# 10-ESP32.net
KiCad netlist of a schematic drawn in Altium Designer
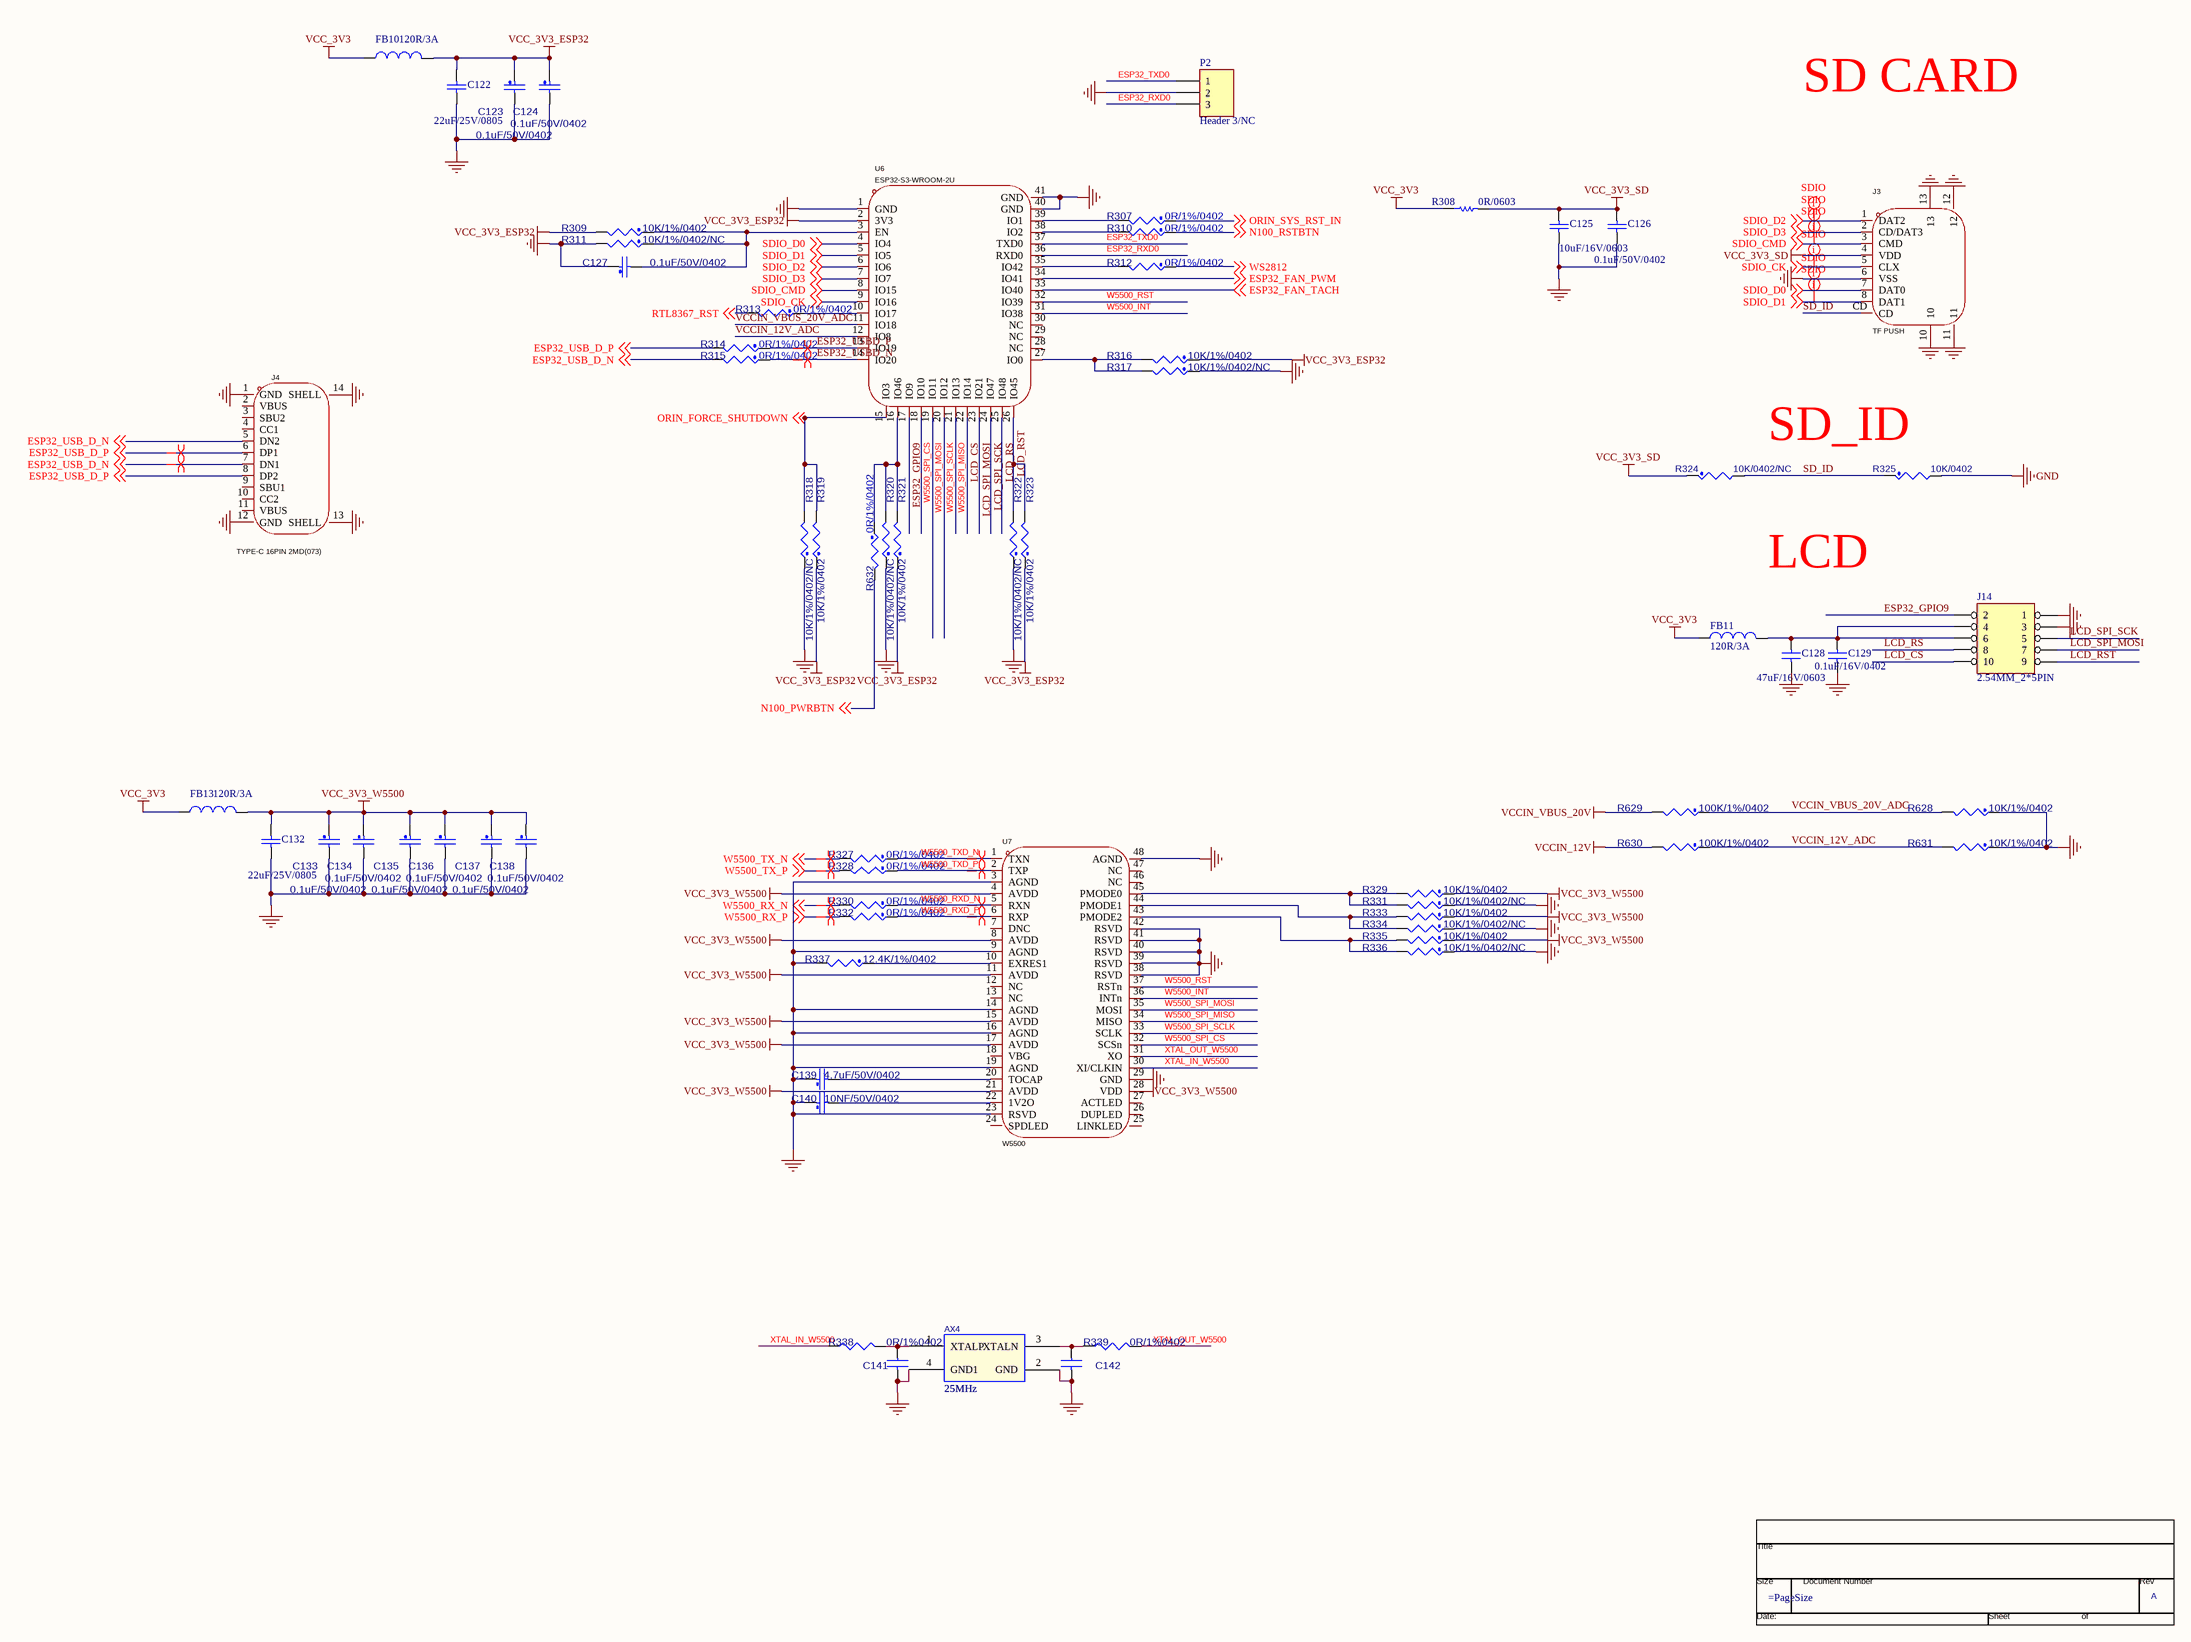
[diagram p0: 10-ESP32.SchDoc]

(export (version "E")
  (design (tool "Eeschema 10.0.6"))
  (components
    (comp (ref "AX4")
      (value "25MHz")
      (footprint "2016")
      (fields (field (name "ALTIUM_VALUE") "25MHz"))
      (libsource (lib "*") (part "XTAL_0"))
    )
    (comp (ref "C122")
      (value "22uF/25V/0805")
      (description "Capacitor")
      (fields (field (name "PUBLISHER") "Altium Limited"))
      (libsource (lib "LIBS") (part "CAP"))
    )
    (comp (ref "C123")
      (value "0.1uF/50V/0402")
      (footprint "C0402")
      (description "GCM155R71H104KE02/MURATA")
      (fields (field (name "TOLERANCE") "10%") (field (name "VOLTAGE") "16V"))
      (libsource (lib "*") (part "CAP_NP"))
    )
    (comp (ref "C124")
      (value "0.1uF/50V/0402")
      (footprint "C0402")
      (description "GCM155R71H104KE02/MURATA")
      (fields (field (name "TOLERANCE") "10%") (field (name "VOLTAGE") "16V"))
      (libsource (lib "*") (part "CAP_NP"))
    )
    (comp (ref "C125")
      (value "10uF/16V/0603")
      (description "Capacitor")
      (fields (field (name "Comment") "HGC0603R5106M160NTHJ") (field (name "PUBLISHER") "Altium Limited"))
      (libsource (lib "LIBS") (part "CAP"))
    )
    (comp (ref "C126")
      (value "0.1uF/50V/0402")
      (description "Capacitor")
      (fields (field (name "PUBLISHER") "Altium Limited"))
      (libsource (lib "LIBS") (part "CAP"))
    )
    (comp (ref "C127")
      (value "0.1uF/50V/0402")
      (footprint "C0402")
      (description "GCM155R71H104KE02/MURATA")
      (fields (field (name "TOLERANCE") "10%") (field (name "VOLTAGE") "16V"))
      (libsource (lib "*") (part "CAP_NP"))
    )
    (comp (ref "C128")
      (value "47uF/16V/0603")
      (description "Capacitor")
      (fields (field (name "PUBLISHER") "Altium Limited"))
      (libsource (lib "LIBS") (part "CAP"))
    )
    (comp (ref "C129")
      (value "0.1uF/16V/0402")
      (description "Capacitor")
      (fields (field (name "PUBLISHER") "Altium Limited"))
      (libsource (lib "LIBS") (part "CAP"))
    )
    (comp (ref "C132")
      (value "22uF/25V/0805")
      (description "Capacitor")
      (fields (field (name "PUBLISHER") "Altium Limited"))
      (libsource (lib "LIBS") (part "CAP"))
    )
    (comp (ref "C133")
      (value "0.1uF/50V/0402")
      (footprint "C0402")
      (description "GCM155R71H104KE02/MURATA")
      (fields (field (name "TOLERANCE") "10%") (field (name "VOLTAGE") "16V"))
      (libsource (lib "*") (part "CAP_NP"))
    )
    (comp (ref "C134")
      (value "0.1uF/50V/0402")
      (footprint "C0402")
      (description "GCM155R71H104KE02/MURATA")
      (fields (field (name "TOLERANCE") "10%") (field (name "VOLTAGE") "16V"))
      (libsource (lib "*") (part "CAP_NP"))
    )
    (comp (ref "C135")
      (value "0.1uF/50V/0402")
      (footprint "C0402")
      (description "GCM155R71H104KE02/MURATA")
      (fields (field (name "TOLERANCE") "10%") (field (name "VOLTAGE") "16V"))
      (libsource (lib "*") (part "CAP_NP"))
    )
    (comp (ref "C136")
      (value "0.1uF/50V/0402")
      (footprint "C0402")
      (description "GCM155R71H104KE02/MURATA")
      (fields (field (name "TOLERANCE") "10%") (field (name "VOLTAGE") "16V"))
      (libsource (lib "*") (part "CAP_NP"))
    )
    (comp (ref "C137")
      (value "0.1uF/50V/0402")
      (footprint "C0402")
      (description "GCM155R71H104KE02/MURATA")
      (fields (field (name "TOLERANCE") "10%") (field (name "VOLTAGE") "16V"))
      (libsource (lib "*") (part "CAP_NP"))
    )
    (comp (ref "C138")
      (value "0.1uF/50V/0402")
      (footprint "C0402")
      (description "GCM155R71H104KE02/MURATA")
      (fields (field (name "TOLERANCE") "10%") (field (name "VOLTAGE") "16V"))
      (libsource (lib "*") (part "CAP_NP"))
    )
    (comp (ref "C139")
      (value "4.7uF/50V/0402")
      (footprint "C0402")
      (description "GCM155R71H104KE02/MURATA")
      (fields (field (name "TOLERANCE") "10%") (field (name "VOLTAGE") "16V"))
      (libsource (lib "*") (part "CAP_NP"))
    )
    (comp (ref "C140")
      (value "10NF/50V/0402")
      (footprint "C0402")
      (description "GCM155R71H104KE02/MURATA")
      (fields (field (name "TOLERANCE") "10%") (field (name "VOLTAGE") "16V"))
      (libsource (lib "*") (part "CAP_NP"))
    )
    (comp (ref "C141") (value "CAP NP_Dup3") (footprint "C0402") (libsource (lib "*") (part "CAP NP_Dup3")))
    (comp (ref "C142") (value "CAP NP_Dup3") (footprint "C0402") (libsource (lib "*") (part "CAP NP_Dup3")))
    (comp (ref "FB10")
      (value "120R/3A")
      (footprint "L0603")
      (description "BLM18KG121TN1D")
      (fields (field (name "PUBLISHER") "Altium Limited"))
      (libsource (lib "") (part "Inductor_1"))
    )
    (comp (ref "FB11")
      (value "120R/3A")
      (footprint "L0603")
      (description "BLM18KG121TN1D")
      (fields (field (name "PUBLISHER") "Altium Limited"))
      (libsource (lib "LIBS") (part "Inductor"))
    )
    (comp (ref "FB13")
      (value "120R/3A")
      (footprint "L0603")
      (description "BLM18KG121TN1D")
      (fields (field (name "PUBLISHER") "Altium Limited"))
      (libsource (lib "") (part "Inductor_1"))
    )
    (comp (ref "J3")
      (value "TF PUSH")
      (footprint "TF-SMD_TF-PUSH")
      (fields (field (name "MANUFACTURER") "SHOU HAN(首韩)"))
      (libsource (lib "altium-import") (part "root_0_TF PUSH_"))
    )
    (comp (ref "J4")
      (value "TYPE-C 16PIN 2MD(073)")
      (footprint "USB-C-SMD_TYPE-C-6PIN-2MD-073")
      (fields (field (name "MANUFACTURER") "SHOU HAN(首韩)"))
      (libsource (lib "altium-import") (part "root_0_TYPE-C 16PIN 2MD(073)_"))
    )
    (comp (ref "J14")
      (value "2.54MM_2*5PIN")
      (footprint "IDC10")
      (libsource (lib "LIBS") (part "HEADER 5X2"))
    )
    (comp (ref "P2")
      (value "Header 3/NC")
      (footprint "HEADER3")
      (description "Header, 3-Pin")
      (fields (field (name "PUBLISHER") "Altium Limited"))
      (libsource (lib "LIBS") (part "Header 3"))
    )
    (comp (ref "R307")
      (value "0R/1%/0402")
      (footprint "R0402")
      (description "AC0402FR-070RL/YAGEO")
      (fields (field (name "TOLERANCE") "1%") (field (name "Comment") "RES_Dup2"))
      (libsource (lib "*") (part "RES_Dup2"))
    )
    (comp (ref "R308")
      (value "0R/0603")
      (footprint "R0603")
      (description "Semiconductor Resistor")
      (fields (field (name "PUBLISHER") "Altium Limited"))
      (libsource (lib "LIBS") (part "Res Semi"))
    )
    (comp (ref "R309")
      (value "10K/1%/0402")
      (footprint "R0402")
      (description "AC0402FR-0710KL/YAGEO")
      (fields (field (name "Comment") "RES_Dup2"))
      (libsource (lib "*") (part "RES_Dup2"))
    )
    (comp (ref "R310")
      (value "0R/1%/0402")
      (footprint "R0402")
      (description "AC0402FR-070RL/YAGEO")
      (fields (field (name "TOLERANCE") "1%") (field (name "Comment") "RES_Dup2"))
      (libsource (lib "*") (part "RES_Dup2"))
    )
    (comp (ref "R311")
      (value "10K/1%/0402/NC")
      (footprint "R0402")
      (description "AC0402FR-0710KL/YAGEO")
      (fields (field (name "Comment") "RES_Dup2"))
      (libsource (lib "*") (part "RES_Dup2"))
    )
    (comp (ref "R312")
      (value "0R/1%/0402")
      (footprint "R0402")
      (description "AC0402FR-070RL/YAGEO")
      (fields (field (name "TOLERANCE") "1%") (field (name "Comment") "RES_Dup2"))
      (libsource (lib "*") (part "RES_Dup2"))
    )
    (comp (ref "R313")
      (value "0R/1%/0402")
      (footprint "R0402")
      (description "AC0402FR-070RL/YAGEO")
      (fields (field (name "TOLERANCE") "1%") (field (name "Comment") "RES_Dup2"))
      (libsource (lib "*") (part "RES_Dup2"))
    )
    (comp (ref "R314")
      (value "0R/1%/0402")
      (footprint "R0402")
      (description "AC0402FR-070RL/YAGEO")
      (fields (field (name "TOLERANCE") "1%") (field (name "Comment") "RES_Dup2"))
      (libsource (lib "*") (part "RES_Dup2"))
    )
    (comp (ref "R315")
      (value "0R/1%/0402")
      (footprint "R0402")
      (description "AC0402FR-070RL/YAGEO")
      (fields (field (name "TOLERANCE") "1%") (field (name "Comment") "RES_Dup2"))
      (libsource (lib "*") (part "RES_Dup2"))
    )
    (comp (ref "R316")
      (value "10K/1%/0402")
      (footprint "R0402")
      (description "AC0402FR-0710KL/YAGEO")
      (fields (field (name "Comment") "RES_Dup2"))
      (libsource (lib "*") (part "RES_Dup2"))
    )
    (comp (ref "R317")
      (value "10K/1%/0402/NC")
      (footprint "R0402")
      (description "AC0402FR-0710KL/YAGEO")
      (fields (field (name "Comment") "RES_Dup2"))
      (libsource (lib "*") (part "RES_Dup2"))
    )
    (comp (ref "R318")
      (value "10K/1%/0402/NC")
      (footprint "R0402")
      (description "AC0402FR-0710KL/YAGEO")
      (fields (field (name "Comment") "RES_Dup2"))
      (libsource (lib "*") (part "RES_Dup2"))
    )
    (comp (ref "R319")
      (value "10K/1%/0402")
      (footprint "R0402")
      (description "AC0402FR-0710KL/YAGEO")
      (fields (field (name "Comment") "RES_Dup2"))
      (libsource (lib "*") (part "RES_Dup2"))
    )
    (comp (ref "R320")
      (value "10K/1%/0402/NC")
      (footprint "R0402")
      (description "AC0402FR-0710KL/YAGEO")
      (fields (field (name "Comment") "RES_Dup2"))
      (libsource (lib "*") (part "RES_Dup2"))
    )
    (comp (ref "R321")
      (value "10K/1%/0402")
      (footprint "R0402")
      (description "AC0402FR-0710KL/YAGEO")
      (fields (field (name "Comment") "RES_Dup2"))
      (libsource (lib "*") (part "RES_Dup2"))
    )
    (comp (ref "R322")
      (value "10K/1%/0402/NC")
      (footprint "R0402")
      (description "AC0402FR-0710KL/YAGEO")
      (fields (field (name "Comment") "RES_Dup2"))
      (libsource (lib "*") (part "RES_Dup2"))
    )
    (comp (ref "R323")
      (value "10K/1%/0402")
      (footprint "R0402")
      (description "AC0402FR-0710KL/YAGEO")
      (fields (field (name "Comment") "RES_Dup2"))
      (libsource (lib "*") (part "RES_Dup2"))
    )
    (comp (ref "R324")
      (value "10K/0402/NC")
      (footprint "R0402")
      (description "RES MF 1.0K 1/16W 5% 0402")
      (fields (field (name "TOLERANCE") "5%"))
      (libsource (lib "*") (part "RES_Dup1"))
    )
    (comp (ref "R325")
      (value "10K/0402")
      (footprint "R0402")
      (description "RES MF 1.0K 1/16W 5% 0402")
      (fields (field (name "TOLERANCE") "5%"))
      (libsource (lib "*") (part "RES_Dup1"))
    )
    (comp (ref "R327")
      (value "0R/1%/0402")
      (footprint "R0402")
      (description "AC0402FR-070RL/YAGEO")
      (fields (field (name "TOLERANCE") "1%") (field (name "Comment") "RES_Dup2"))
      (libsource (lib "*") (part "RES_Dup2"))
    )
    (comp (ref "R328")
      (value "0R/1%/0402")
      (footprint "R0402")
      (description "AC0402FR-070RL/YAGEO")
      (fields (field (name "TOLERANCE") "1%") (field (name "Comment") "RES_Dup2"))
      (libsource (lib "*") (part "RES_Dup2"))
    )
    (comp (ref "R329")
      (value "10K/1%/0402")
      (footprint "R0402")
      (description "AC0402FR-0710KL/YAGEO")
      (fields (field (name "Comment") "RES_Dup2"))
      (libsource (lib "*") (part "RES_Dup2"))
    )
    (comp (ref "R330")
      (value "0R/1%/0402")
      (footprint "R0402")
      (description "AC0402FR-070RL/YAGEO")
      (fields (field (name "TOLERANCE") "1%") (field (name "Comment") "RES_Dup2"))
      (libsource (lib "*") (part "RES_Dup2"))
    )
    (comp (ref "R331")
      (value "10K/1%/0402/NC")
      (footprint "R0402")
      (description "AC0402FR-0710KL/YAGEO")
      (fields (field (name "Comment") "RES_Dup2"))
      (libsource (lib "*") (part "RES_Dup2"))
    )
    (comp (ref "R332")
      (value "0R/1%/0402")
      (footprint "R0402")
      (description "AC0402FR-070RL/YAGEO")
      (fields (field (name "TOLERANCE") "1%") (field (name "Comment") "RES_Dup2"))
      (libsource (lib "*") (part "RES_Dup2"))
    )
    (comp (ref "R333")
      (value "10K/1%/0402")
      (footprint "R0402")
      (description "AC0402FR-0710KL/YAGEO")
      (fields (field (name "Comment") "RES_Dup2"))
      (libsource (lib "*") (part "RES_Dup2"))
    )
    (comp (ref "R334")
      (value "10K/1%/0402/NC")
      (footprint "R0402")
      (description "AC0402FR-0710KL/YAGEO")
      (fields (field (name "Comment") "RES_Dup2"))
      (libsource (lib "*") (part "RES_Dup2"))
    )
    (comp (ref "R335")
      (value "10K/1%/0402")
      (footprint "R0402")
      (description "AC0402FR-0710KL/YAGEO")
      (fields (field (name "Comment") "RES_Dup2"))
      (libsource (lib "*") (part "RES_Dup2"))
    )
    (comp (ref "R336")
      (value "10K/1%/0402/NC")
      (footprint "R0402")
      (description "AC0402FR-0710KL/YAGEO")
      (fields (field (name "Comment") "RES_Dup2"))
      (libsource (lib "*") (part "RES_Dup2"))
    )
    (comp (ref "R337")
      (value "12.4K/1%/0402")
      (footprint "R0402")
      (description "AC0402FR-0710KL/YAGEO")
      (fields (field (name "Comment") "RES_Dup2"))
      (libsource (lib "*") (part "RES_Dup2"))
    )
    (comp (ref "R338")
      (value "0R/1%0402")
      (footprint "R0402")
      (fields (field (name "Comment") "R_Dup3"))
      (libsource (lib "*") (part "R_Dup3"))
    )
    (comp (ref "R339")
      (value "0R/1%0402")
      (footprint "R0402")
      (fields (field (name "Comment") "R_Dup3"))
      (libsource (lib "*") (part "R_Dup3"))
    )
    (comp (ref "R628")
      (value "10K/1%/0402")
      (footprint "R0402")
      (description "AC0402FR-0710KL/YAGEO")
      (fields (field (name "Comment") "RES_Dup2"))
      (libsource (lib "*") (part "RES_Dup2"))
    )
    (comp (ref "R629")
      (value "100K/1%/0402")
      (footprint "R0402")
      (description "AC0402FR-0710KL/YAGEO")
      (fields (field (name "Comment") "RES_Dup2"))
      (libsource (lib "*") (part "RES_Dup2"))
    )
    (comp (ref "R630")
      (value "100K/1%/0402")
      (footprint "R0402")
      (description "AC0402FR-0710KL/YAGEO")
      (fields (field (name "Comment") "RES_Dup2"))
      (libsource (lib "*") (part "RES_Dup2"))
    )
    (comp (ref "R631")
      (value "10K/1%/0402")
      (footprint "R0402")
      (description "AC0402FR-0710KL/YAGEO")
      (fields (field (name "Comment") "RES_Dup2"))
      (libsource (lib "*") (part "RES_Dup2"))
    )
    (comp (ref "R632")
      (value "0R/1%/0402")
      (footprint "R0402")
      (description "AC0402FR-070RL/YAGEO")
      (fields (field (name "TOLERANCE") "1%") (field (name "Comment") "RES_Dup2"))
      (libsource (lib "*") (part "RES_Dup2"))
    )
    (comp (ref "U6")
      (value "ESP32-S3-WROOM-2U")
      (footprint "ESP32-S3-WROOM-2")
      (fields
        (field (name "MANUFACTURER") "ESPRESSIF(乐鑫)")
        (field (name "MANUFACTURER PART") "ESP32-S3-WROOM-2-N32R8V")
      )
      (libsource (lib "altium-import") (part "root_0_ESP32-S3-WROOM-2-N32R8V_"))
    )
    (comp (ref "U7")
      (value "W5500")
      (footprint "LQFP-48_L7.0-W7.0-P0.50-LS9.0-BL")
      (fields (field (name "MANUFACTURER") "WIZNET"))
      (libsource (lib "altium-import") (part "root_0_W5500_"))
    )
  )
  (nets
    (net (code "1") (name "/ESP32_GPIO9") (class "Default")
      (node (ref "J14") (pin "2") (pinfunction "2_2") (pintype "passive"))
      (node (ref "U6") (pin "17") (pinfunction "IO9_17") (pintype "passive"))
    )
    (net (code "2") (name "/ESP32_RXD0") (class "Default")
      (node (ref "P2") (pin "3") (pinfunction "3_3") (pintype "passive"))
      (node (ref "U6") (pin "36") (pinfunction "RXD0_36") (pintype "passive"))
    )
    (net (code "3") (name "/ESP32_TXD0") (class "Default")
      (node (ref "P2") (pin "1") (pinfunction "1_1") (pintype "passive"))
      (node (ref "U6") (pin "37") (pinfunction "TXD0_37") (pintype "passive"))
    )
    (net (code "4") (name "/ESP32_USBD_N") (class "Default")
      (node (ref "R315") (pin "1") (pinfunction "1_1") (pintype "passive"))
      (node (ref "U6") (pin "14") (pinfunction "IO20_14") (pintype "passive"))
    )
    (net (code "5") (name "/ESP32_USBD_P") (class "Default")
      (node (ref "R314") (pin "1") (pinfunction "1_1") (pintype "passive"))
      (node (ref "U6") (pin "13") (pinfunction "IO19_13") (pintype "passive"))
    )
    (net (code "6") (name "/LCD_CS") (class "Default")
      (node (ref "J14") (pin "10") (pinfunction "10_10") (pintype "passive"))
      (node (ref "U6") (pin "22") (pinfunction "IO14_22") (pintype "passive"))
    )
    (net (code "7") (name "/LCD_RS") (class "Default")
      (node (ref "J14") (pin "8") (pinfunction "8_8") (pintype "passive"))
      (node (ref "U6") (pin "25") (pinfunction "IO48_25") (pintype "passive"))
    )
    (net (code "8") (name "/LCD_RST") (class "Default")
      (node (ref "J14") (pin "9") (pinfunction "9_9") (pintype "passive"))
      (node (ref "R322") (pin "2") (pinfunction "2_2") (pintype "passive"))
      (node (ref "R323") (pin "2") (pinfunction "2_2") (pintype "passive"))
      (node (ref "U6") (pin "26") (pinfunction "IO45_26") (pintype "passive"))
    )
    (net (code "9") (name "/LCD_SPI_MOSI") (class "Default")
      (node (ref "J14") (pin "7") (pinfunction "7_7") (pintype "passive"))
      (node (ref "U6") (pin "23") (pinfunction "IO21_23") (pintype "passive"))
    )
    (net (code "10") (name "/LCD_SPI_SCK") (class "Default")
      (node (ref "J14") (pin "5") (pinfunction "5_5") (pintype "passive"))
      (node (ref "U6") (pin "24") (pinfunction "IO47_24") (pintype "passive"))
    )
    (net (code "11") (name "/SD_ID") (class "Default")
      (node (ref "J3") (pin "CD") (pinfunction "CD_CD") (pintype "passive"))
      (node (ref "R324") (pin "2") (pinfunction "2_2") (pintype "passive"))
      (node (ref "R325") (pin "1") (pinfunction "1_1") (pintype "passive"))
    )
    (net (code "12") (name "/VCCIN_12V_ADC") (class "Default")
      (node (ref "R630") (pin "1") (pinfunction "1_1") (pintype "passive"))
      (node (ref "R631") (pin "2") (pinfunction "2_2") (pintype "passive"))
      (node (ref "U6") (pin "12") (pinfunction "IO8_12") (pintype "passive"))
    )
    (net (code "13") (name "/VCCIN_VBUS_20V_ADC") (class "Default")
      (node (ref "R628") (pin "2") (pinfunction "2_2") (pintype "passive"))
      (node (ref "R629") (pin "1") (pinfunction "1_1") (pintype "passive"))
      (node (ref "U6") (pin "11") (pinfunction "IO18_11") (pintype "passive"))
    )
    (net (code "14") (name "/W5500_INT") (class "Default")
      (node (ref "U6") (pin "31") (pinfunction "IO38_31") (pintype "passive"))
      (node (ref "U7") (pin "36") (pinfunction "INTn_36") (pintype "passive"))
    )
    (net (code "15") (name "/W5500_RST") (class "Default")
      (node (ref "U6") (pin "32") (pinfunction "IO39_32") (pintype "passive"))
      (node (ref "U7") (pin "37") (pinfunction "RSTn_37") (pintype "passive"))
    )
    (net (code "16") (name "/W5500_RXD_N") (class "Default")
      (node (ref "R330") (pin "1") (pinfunction "1_1") (pintype "passive"))
      (node (ref "U7") (pin "5") (pinfunction "RXN_5") (pintype "passive"))
    )
    (net (code "17") (name "/W5500_RXD_P") (class "Default")
      (node (ref "R332") (pin "1") (pinfunction "1_1") (pintype "passive"))
      (node (ref "U7") (pin "6") (pinfunction "RXP_6") (pintype "passive"))
    )
    (net (code "18") (name "/W5500_SPI_CS") (class "Default")
      (node (ref "U6") (pin "18") (pinfunction "IO10_18") (pintype "passive"))
      (node (ref "U7") (pin "32") (pinfunction "SCSn_32") (pintype "passive"))
    )
    (net (code "19") (name "/W5500_SPI_MISO") (class "Default")
      (node (ref "U6") (pin "21") (pinfunction "IO13_21") (pintype "passive"))
      (node (ref "U7") (pin "34") (pinfunction "MISO_34") (pintype "passive"))
    )
    (net (code "20") (name "/W5500_SPI_MOSI") (class "Default")
      (node (ref "U6") (pin "19") (pinfunction "IO11_19") (pintype "passive"))
      (node (ref "U7") (pin "35") (pinfunction "MOSI_35") (pintype "passive"))
    )
    (net (code "21") (name "/W5500_SPI_SCLK") (class "Default")
      (node (ref "U6") (pin "20") (pinfunction "IO12_20") (pintype "passive"))
      (node (ref "U7") (pin "33") (pinfunction "SCLK_33") (pintype "passive"))
    )
    (net (code "22") (name "/W5500_TXD_N") (class "Default")
      (node (ref "R327") (pin "1") (pinfunction "1_1") (pintype "passive"))
      (node (ref "U7") (pin "1") (pinfunction "TXN_1") (pintype "passive"))
    )
    (net (code "23") (name "/W5500_TXD_P") (class "Default")
      (node (ref "R328") (pin "1") (pinfunction "1_1") (pintype "passive"))
      (node (ref "U7") (pin "2") (pinfunction "TXP_2") (pintype "passive"))
    )
    (net (code "24") (name "/XTAL_IN_W5500") (class "Default")
      (node (ref "R338") (pin "1") (pinfunction "1_1") (pintype "passive"))
      (node (ref "U7") (pin "30") (pinfunction "XI/CLKIN_30") (pintype "passive"))
    )
    (net (code "25") (name "/XTAL_OUT_W5500") (class "Default")
      (node (ref "R339") (pin "2") (pinfunction "2_2") (pintype "passive"))
      (node (ref "U7") (pin "31") (pinfunction "XO_31") (pintype "passive"))
    )
    (net (code "26") (name "ESP32_FAN_PWM") (class "Default")
      (node (ref "U6") (pin "34") (pinfunction "IO41_34") (pintype "passive"))
    )
    (net (code "27") (name "ESP32_FAN_TACH") (class "Default")
      (node (ref "U6") (pin "33") (pinfunction "IO40_33") (pintype "passive"))
    )
    (net (code "28") (name "ESP32_USB_D_N") (class "Default")
      (node (ref "J4") (pin "5") (pinfunction "DN2_5") (pintype "passive"))
      (node (ref "J4") (pin "7") (pinfunction "DN1_7") (pintype "passive"))
      (node (ref "R315") (pin "2") (pinfunction "2_2") (pintype "passive"))
    )
    (net (code "29") (name "ESP32_USB_D_P") (class "Default")
      (node (ref "J4") (pin "6") (pinfunction "DP1_6") (pintype "passive"))
      (node (ref "J4") (pin "8") (pinfunction "DP2_8") (pintype "passive"))
      (node (ref "R314") (pin "2") (pinfunction "2_2") (pintype "passive"))
    )
    (net (code "30") (name "GND") (class "Default")
      (node (ref "AX4") (pin "2") (pinfunction "GND_2") (pintype "passive"))
      (node (ref "AX4") (pin "4") (pinfunction "GND1_4") (pintype "passive"))
      (node (ref "C122") (pin "1") (pinfunction "1_1") (pintype "passive"))
      (node (ref "C123") (pin "2") (pinfunction "2_2") (pintype "passive"))
      (node (ref "C124") (pin "2") (pinfunction "2_2") (pintype "passive"))
      (node (ref "C125") (pin "1") (pinfunction "1_1") (pintype "passive"))
      (node (ref "C126") (pin "1") (pinfunction "1_1") (pintype "passive"))
      (node (ref "C127") (pin "1") (pinfunction "1_1") (pintype "passive"))
      (node (ref "C128") (pin "1") (pinfunction "1_1") (pintype "passive"))
      (node (ref "C129") (pin "1") (pinfunction "1_1") (pintype "passive"))
      (node (ref "C132") (pin "1") (pinfunction "1_1") (pintype "passive"))
      (node (ref "C133") (pin "2") (pinfunction "2_2") (pintype "passive"))
      (node (ref "C134") (pin "2") (pinfunction "2_2") (pintype "passive"))
      (node (ref "C135") (pin "2") (pinfunction "2_2") (pintype "passive"))
      (node (ref "C136") (pin "2") (pinfunction "2_2") (pintype "passive"))
      (node (ref "C137") (pin "2") (pinfunction "2_2") (pintype "passive"))
      (node (ref "C138") (pin "2") (pinfunction "2_2") (pintype "passive"))
      (node (ref "C139") (pin "1") (pinfunction "1_1") (pintype "passive"))
      (node (ref "C140") (pin "1") (pinfunction "1_1") (pintype "passive"))
      (node (ref "C141") (pin "2") (pinfunction "2_2") (pintype "passive"))
      (node (ref "C142") (pin "2") (pinfunction "2_2") (pintype "passive"))
      (node (ref "J14") (pin "1") (pinfunction "1_1") (pintype "passive"))
      (node (ref "J14") (pin "3") (pinfunction "3_3") (pintype "passive"))
      (node (ref "J3") (pin "10") (pinfunction "10_10") (pintype "passive"))
      (node (ref "J3") (pin "11") (pinfunction "11_11") (pintype "passive"))
      (node (ref "J3") (pin "12") (pinfunction "12_12") (pintype "passive"))
      (node (ref "J3") (pin "13") (pinfunction "13_13") (pintype "passive"))
      (node (ref "J3") (pin "6") (pinfunction "VSS_6") (pintype "passive"))
      (node (ref "J4") (pin "1") (pinfunction "GND_1") (pintype "passive"))
      (node (ref "J4") (pin "12") (pinfunction "GND_12") (pintype "passive"))
      (node (ref "J4") (pin "13") (pinfunction "SHELL_13") (pintype "passive"))
      (node (ref "J4") (pin "14") (pinfunction "SHELL_14") (pintype "passive"))
      (node (ref "P2") (pin "2") (pinfunction "2_2") (pintype "passive"))
      (node (ref "R311") (pin "2") (pinfunction "2_2") (pintype "passive"))
      (node (ref "R317") (pin "1") (pinfunction "1_1") (pintype "passive"))
      (node (ref "R318") (pin "1") (pinfunction "1_1") (pintype "passive"))
      (node (ref "R320") (pin "1") (pinfunction "1_1") (pintype "passive"))
      (node (ref "R322") (pin "1") (pinfunction "1_1") (pintype "passive"))
      (node (ref "R325") (pin "2") (pinfunction "2_2") (pintype "passive"))
      (node (ref "R331") (pin "1") (pinfunction "1_1") (pintype "passive"))
      (node (ref "R334") (pin "1") (pinfunction "1_1") (pintype "passive"))
      (node (ref "R336") (pin "1") (pinfunction "1_1") (pintype "passive"))
      (node (ref "R337") (pin "2") (pinfunction "2_2") (pintype "passive"))
      (node (ref "R628") (pin "1") (pinfunction "1_1") (pintype "passive"))
      (node (ref "R631") (pin "1") (pinfunction "1_1") (pintype "passive"))
      (node (ref "U6") (pin "1") (pinfunction "GND_1") (pintype "passive"))
      (node (ref "U6") (pin "40") (pinfunction "GND_40") (pintype "passive"))
      (node (ref "U6") (pin "41") (pinfunction "GND_41") (pintype "passive"))
      (node (ref "U7") (pin "14") (pinfunction "AGND_14") (pintype "passive"))
      (node (ref "U7") (pin "16") (pinfunction "AGND_16") (pintype "passive"))
      (node (ref "U7") (pin "19") (pinfunction "AGND_19") (pintype "passive"))
      (node (ref "U7") (pin "23") (pinfunction "RSVD_23") (pintype "passive"))
      (node (ref "U7") (pin "29") (pinfunction "GND_29") (pintype "passive"))
      (node (ref "U7") (pin "3") (pinfunction "AGND_3") (pintype "passive"))
      (node (ref "U7") (pin "38") (pinfunction "RSVD_38") (pintype "passive"))
      (node (ref "U7") (pin "39") (pinfunction "RSVD_39") (pintype "passive"))
      (node (ref "U7") (pin "40") (pinfunction "RSVD_40") (pintype "passive"))
      (node (ref "U7") (pin "41") (pinfunction "RSVD_41") (pintype "passive"))
      (node (ref "U7") (pin "42") (pinfunction "RSVD_42") (pintype "passive"))
      (node (ref "U7") (pin "48") (pinfunction "AGND_48") (pintype "passive"))
      (node (ref "U7") (pin "9") (pinfunction "AGND_9") (pintype "passive"))
    )
    (net (code "31") (name "N100_PWRBTN") (class "Default")
      (node (ref "R632") (pin "2") (pinfunction "2_2") (pintype "passive"))
    )
    (net (code "32") (name "N100_RSTBTN") (class "Default")
      (node (ref "R310") (pin "1") (pinfunction "1_1") (pintype "passive"))
    )
    (net (code "33") (name "Net-(AX4-XTALN)") (class "Default")
      (node (ref "AX4") (pin "3") (pinfunction "XTALN_3") (pintype "passive"))
      (node (ref "C142") (pin "1") (pinfunction "1_1") (pintype "passive"))
      (node (ref "R339") (pin "1") (pinfunction "1_1") (pintype "passive"))
    )
    (net (code "34") (name "Net-(AX4-XTALP)") (class "Default")
      (node (ref "AX4") (pin "1") (pinfunction "XTALP_1") (pintype "passive"))
      (node (ref "C141") (pin "1") (pinfunction "1_1") (pintype "passive"))
      (node (ref "R338") (pin "2") (pinfunction "2_2") (pintype "passive"))
    )
    (net (code "35") (name "Net-(C128-Pad2)") (class "Default")
      (node (ref "C128") (pin "2") (pinfunction "2_2") (pintype "passive"))
      (node (ref "C129") (pin "2") (pinfunction "2_2") (pintype "passive"))
      (node (ref "FB11") (pin "1") (pinfunction "1_1") (pintype "passive"))
      (node (ref "J14") (pin "4") (pinfunction "4_4") (pintype "passive"))
      (node (ref "J14") (pin "6") (pinfunction "6_6") (pintype "passive"))
    )
    (net (code "36") (name "Net-(U6-EN)") (class "Default")
      (node (ref "C127") (pin "2") (pinfunction "2_2") (pintype "passive"))
      (node (ref "R309") (pin "1") (pinfunction "1_1") (pintype "passive"))
      (node (ref "R311") (pin "1") (pinfunction "1_1") (pintype "passive"))
      (node (ref "U6") (pin "3") (pinfunction "EN_3") (pintype "passive"))
    )
    (net (code "37") (name "Net-(U6-IO0)") (class "Default")
      (node (ref "R316") (pin "2") (pinfunction "2_2") (pintype "passive"))
      (node (ref "R317") (pin "2") (pinfunction "2_2") (pintype "passive"))
      (node (ref "U6") (pin "27") (pinfunction "IO0_27") (pintype "passive"))
    )
    (net (code "38") (name "Net-(U6-IO1)") (class "Default")
      (node (ref "R307") (pin "2") (pinfunction "2_2") (pintype "passive"))
      (node (ref "U6") (pin "39") (pinfunction "IO1_39") (pintype "passive"))
    )
    (net (code "39") (name "Net-(U6-IO2)") (class "Default")
      (node (ref "R310") (pin "2") (pinfunction "2_2") (pintype "passive"))
      (node (ref "U6") (pin "38") (pinfunction "IO2_38") (pintype "passive"))
    )
    (net (code "40") (name "Net-(U6-IO17)") (class "Default")
      (node (ref "R313") (pin "1") (pinfunction "1_1") (pintype "passive"))
      (node (ref "U6") (pin "10") (pinfunction "IO17_10") (pintype "passive"))
    )
    (net (code "41") (name "Net-(U6-IO42)") (class "Default")
      (node (ref "R312") (pin "2") (pinfunction "2_2") (pintype "passive"))
      (node (ref "U6") (pin "35") (pinfunction "IO42_35") (pintype "passive"))
    )
    (net (code "42") (name "Net-(U6-IO46)") (class "Default")
      (node (ref "R320") (pin "2") (pinfunction "2_2") (pintype "passive"))
      (node (ref "R321") (pin "2") (pinfunction "2_2") (pintype "passive"))
      (node (ref "R632") (pin "1") (pinfunction "1_1") (pintype "passive"))
      (node (ref "U6") (pin "16") (pinfunction "IO46_16") (pintype "passive"))
    )
    (net (code "43") (name "Net-(U7-1V2O)") (class "Default")
      (node (ref "C140") (pin "2") (pinfunction "2_2") (pintype "passive"))
      (node (ref "U7") (pin "22") (pinfunction "1V2O_22") (pintype "passive"))
    )
    (net (code "44") (name "Net-(U7-EXRES1)") (class "Default")
      (node (ref "R337") (pin "1") (pinfunction "1_1") (pintype "passive"))
      (node (ref "U7") (pin "10") (pinfunction "EXRES1_10") (pintype "passive"))
    )
    (net (code "45") (name "Net-(U7-PMODE0)") (class "Default")
      (node (ref "R329") (pin "2") (pinfunction "2_2") (pintype "passive"))
      (node (ref "R331") (pin "2") (pinfunction "2_2") (pintype "passive"))
      (node (ref "U7") (pin "45") (pinfunction "PMODE0_45") (pintype "passive"))
    )
    (net (code "46") (name "Net-(U7-PMODE1)") (class "Default")
      (node (ref "R333") (pin "2") (pinfunction "2_2") (pintype "passive"))
      (node (ref "R334") (pin "2") (pinfunction "2_2") (pintype "passive"))
      (node (ref "U7") (pin "44") (pinfunction "PMODE1_44") (pintype "passive"))
    )
    (net (code "47") (name "Net-(U7-PMODE2)") (class "Default")
      (node (ref "R335") (pin "2") (pinfunction "2_2") (pintype "passive"))
      (node (ref "R336") (pin "2") (pinfunction "2_2") (pintype "passive"))
      (node (ref "U7") (pin "43") (pinfunction "PMODE2_43") (pintype "passive"))
    )
    (net (code "48") (name "Net-(U7-TOCAP)") (class "Default")
      (node (ref "C139") (pin "2") (pinfunction "2_2") (pintype "passive"))
      (node (ref "U7") (pin "20") (pinfunction "TOCAP_20") (pintype "passive"))
    )
    (net (code "49") (name "ORIN_FORCE_SHUTDOWN") (class "Default")
      (node (ref "R318") (pin "2") (pinfunction "2_2") (pintype "passive"))
      (node (ref "R319") (pin "2") (pinfunction "2_2") (pintype "passive"))
      (node (ref "U6") (pin "15") (pinfunction "IO3_15") (pintype "passive"))
    )
    (net (code "50") (name "ORIN_SYS_RST_IN") (class "Default")
      (node (ref "R307") (pin "1") (pinfunction "1_1") (pintype "passive"))
    )
    (net (code "51") (name "RTL8367_RST") (class "Default")
      (node (ref "R313") (pin "2") (pinfunction "2_2") (pintype "passive"))
    )
    (net (code "52") (name "SDIO_CK") (class "Default")
      (node (ref "J3") (pin "5") (pinfunction "CLX_5") (pintype "passive"))
      (node (ref "U6") (pin "9") (pinfunction "IO16_9") (pintype "passive"))
    )
    (net (code "53") (name "SDIO_CMD") (class "Default")
      (node (ref "J3") (pin "3") (pinfunction "CMD_3") (pintype "passive"))
      (node (ref "U6") (pin "8") (pinfunction "IO15_8") (pintype "passive"))
    )
    (net (code "54") (name "SDIO_D0") (class "Default")
      (node (ref "J3") (pin "7") (pinfunction "DAT0_7") (pintype "passive"))
      (node (ref "U6") (pin "4") (pinfunction "IO4_4") (pintype "passive"))
    )
    (net (code "55") (name "SDIO_D1") (class "Default")
      (node (ref "J3") (pin "8") (pinfunction "DAT1_8") (pintype "passive"))
      (node (ref "U6") (pin "5") (pinfunction "IO5_5") (pintype "passive"))
    )
    (net (code "56") (name "SDIO_D2") (class "Default")
      (node (ref "J3") (pin "1") (pinfunction "DAT2_1") (pintype "passive"))
      (node (ref "U6") (pin "6") (pinfunction "IO6_6") (pintype "passive"))
    )
    (net (code "57") (name "SDIO_D3") (class "Default")
      (node (ref "J3") (pin "2") (pinfunction "CD/DAT3_2") (pintype "passive"))
      (node (ref "U6") (pin "7") (pinfunction "IO7_7") (pintype "passive"))
    )
    (net (code "58") (name "VCCIN_12V") (class "Default")
      (node (ref "R630") (pin "2") (pinfunction "2_2") (pintype "passive"))
    )
    (net (code "59") (name "VCCIN_VBUS_20V") (class "Default")
      (node (ref "R629") (pin "2") (pinfunction "2_2") (pintype "passive"))
    )
    (net (code "60") (name "VCC_3V3") (class "Default")
      (node (ref "FB10") (pin "1") (pinfunction "1_1") (pintype "passive"))
      (node (ref "FB11") (pin "2") (pinfunction "2_2") (pintype "passive"))
      (node (ref "FB13") (pin "1") (pinfunction "1_1") (pintype "passive"))
      (node (ref "R308") (pin "1") (pinfunction "1_1") (pintype "passive"))
    )
    (net (code "61") (name "VCC_3V3_ESP32") (class "Default")
      (node (ref "C122") (pin "2") (pinfunction "2_2") (pintype "passive"))
      (node (ref "C123") (pin "1") (pinfunction "1_1") (pintype "passive"))
      (node (ref "C124") (pin "1") (pinfunction "1_1") (pintype "passive"))
      (node (ref "FB10") (pin "2") (pinfunction "2_2") (pintype "passive"))
      (node (ref "R309") (pin "2") (pinfunction "2_2") (pintype "passive"))
      (node (ref "R316") (pin "1") (pinfunction "1_1") (pintype "passive"))
      (node (ref "R319") (pin "1") (pinfunction "1_1") (pintype "passive"))
      (node (ref "R321") (pin "1") (pinfunction "1_1") (pintype "passive"))
      (node (ref "R323") (pin "1") (pinfunction "1_1") (pintype "passive"))
      (node (ref "U6") (pin "2") (pinfunction "3V3_2") (pintype "passive"))
    )
    (net (code "62") (name "VCC_3V3_SD") (class "Default")
      (node (ref "C125") (pin "2") (pinfunction "2_2") (pintype "passive"))
      (node (ref "C126") (pin "2") (pinfunction "2_2") (pintype "passive"))
      (node (ref "J3") (pin "4") (pinfunction "VDD_4") (pintype "passive"))
      (node (ref "R308") (pin "2") (pinfunction "2_2") (pintype "passive"))
      (node (ref "R324") (pin "1") (pinfunction "1_1") (pintype "passive"))
    )
    (net (code "63") (name "VCC_3V3_W5500") (class "Default")
      (node (ref "C132") (pin "2") (pinfunction "2_2") (pintype "passive"))
      (node (ref "C133") (pin "1") (pinfunction "1_1") (pintype "passive"))
      (node (ref "C134") (pin "1") (pinfunction "1_1") (pintype "passive"))
      (node (ref "C135") (pin "1") (pinfunction "1_1") (pintype "passive"))
      (node (ref "C136") (pin "1") (pinfunction "1_1") (pintype "passive"))
      (node (ref "C137") (pin "1") (pinfunction "1_1") (pintype "passive"))
      (node (ref "C138") (pin "1") (pinfunction "1_1") (pintype "passive"))
      (node (ref "FB13") (pin "2") (pinfunction "2_2") (pintype "passive"))
      (node (ref "R329") (pin "1") (pinfunction "1_1") (pintype "passive"))
      (node (ref "R333") (pin "1") (pinfunction "1_1") (pintype "passive"))
      (node (ref "R335") (pin "1") (pinfunction "1_1") (pintype "passive"))
      (node (ref "U7") (pin "11") (pinfunction "AVDD_11") (pintype "passive"))
      (node (ref "U7") (pin "15") (pinfunction "AVDD_15") (pintype "passive"))
      (node (ref "U7") (pin "17") (pinfunction "AVDD_17") (pintype "passive"))
      (node (ref "U7") (pin "21") (pinfunction "AVDD_21") (pintype "passive"))
      (node (ref "U7") (pin "28") (pinfunction "VDD_28") (pintype "passive"))
      (node (ref "U7") (pin "4") (pinfunction "AVDD_4") (pintype "passive"))
      (node (ref "U7") (pin "8") (pinfunction "AVDD_8") (pintype "passive"))
    )
    (net (code "64") (name "W5500_RX_N") (class "Default")
      (node (ref "R330") (pin "2") (pinfunction "2_2") (pintype "passive"))
    )
    (net (code "65") (name "W5500_RX_P") (class "Default")
      (node (ref "R332") (pin "2") (pinfunction "2_2") (pintype "passive"))
    )
    (net (code "66") (name "W5500_TX_N") (class "Default")
      (node (ref "R327") (pin "2") (pinfunction "2_2") (pintype "passive"))
    )
    (net (code "67") (name "W5500_TX_P") (class "Default")
      (node (ref "R328") (pin "2") (pinfunction "2_2") (pintype "passive"))
    )
    (net (code "68") (name "WS2812") (class "Default")
      (node (ref "R312") (pin "1") (pinfunction "1_1") (pintype "passive"))
    )
    (net (code "69") (name "unconnected-(J4-CC1-Pad4)") (class "Default")
      (node (ref "J4") (pin "4") (pinfunction "CC1_4") (pintype "passive"))
    )
    (net (code "70") (name "unconnected-(J4-CC2-Pad10)") (class "Default")
      (node (ref "J4") (pin "10") (pinfunction "CC2_10") (pintype "passive"))
    )
    (net (code "71") (name "unconnected-(J4-SBU1-Pad9)") (class "Default")
      (node (ref "J4") (pin "9") (pinfunction "SBU1_9") (pintype "passive"))
    )
    (net (code "72") (name "unconnected-(J4-SBU2-Pad3)") (class "Default")
      (node (ref "J4") (pin "3") (pinfunction "SBU2_3") (pintype "passive"))
    )
    (net (code "73") (name "unconnected-(J4-VBUS-Pad2)") (class "Default")
      (node (ref "J4") (pin "2") (pinfunction "VBUS_2") (pintype "passive"))
    )
    (net (code "74") (name "unconnected-(J4-VBUS-Pad11)") (class "Default")
      (node (ref "J4") (pin "11") (pinfunction "VBUS_11") (pintype "passive"))
    )
    (net (code "75") (name "unconnected-(U6-NC-Pad28)") (class "Default")
      (node (ref "U6") (pin "28") (pinfunction "NC_28") (pintype "passive"))
    )
    (net (code "76") (name "unconnected-(U6-NC-Pad29)") (class "Default")
      (node (ref "U6") (pin "29") (pinfunction "NC_29") (pintype "passive"))
    )
    (net (code "77") (name "unconnected-(U6-NC-Pad30)") (class "Default")
      (node (ref "U6") (pin "30") (pinfunction "NC_30") (pintype "passive"))
    )
    (net (code "78") (name "unconnected-(U7-ACTLED-Pad27)") (class "Default")
      (node (ref "U7") (pin "27") (pinfunction "ACTLED_27") (pintype "passive"))
    )
    (net (code "79") (name "unconnected-(U7-DNC-Pad7)") (class "Default")
      (node (ref "U7") (pin "7") (pinfunction "DNC_7") (pintype "passive"))
    )
    (net (code "80") (name "unconnected-(U7-DUPLED-Pad26)") (class "Default")
      (node (ref "U7") (pin "26") (pinfunction "DUPLED_26") (pintype "passive"))
    )
    (net (code "81") (name "unconnected-(U7-LINKLED-Pad25)") (class "Default")
      (node (ref "U7") (pin "25") (pinfunction "LINKLED_25") (pintype "passive"))
    )
    (net (code "82") (name "unconnected-(U7-NC-Pad12)") (class "Default")
      (node (ref "U7") (pin "12") (pinfunction "NC_12") (pintype "passive"))
    )
    (net (code "83") (name "unconnected-(U7-NC-Pad13)") (class "Default")
      (node (ref "U7") (pin "13") (pinfunction "NC_13") (pintype "passive"))
    )
    (net (code "84") (name "unconnected-(U7-NC-Pad46)") (class "Default")
      (node (ref "U7") (pin "46") (pinfunction "NC_46") (pintype "passive"))
    )
    (net (code "85") (name "unconnected-(U7-NC-Pad47)") (class "Default")
      (node (ref "U7") (pin "47") (pinfunction "NC_47") (pintype "passive"))
    )
    (net (code "86") (name "unconnected-(U7-SPDLED-Pad24)") (class "Default")
      (node (ref "U7") (pin "24") (pinfunction "SPDLED_24") (pintype "passive"))
    )
    (net (code "87") (name "unconnected-(U7-VBG-Pad18)") (class "Default")
      (node (ref "U7") (pin "18") (pinfunction "VBG_18") (pintype "passive"))
    )
  )
)
